# Riso9350e.net
KiCad netlist of a schematic drawn in EAGLE
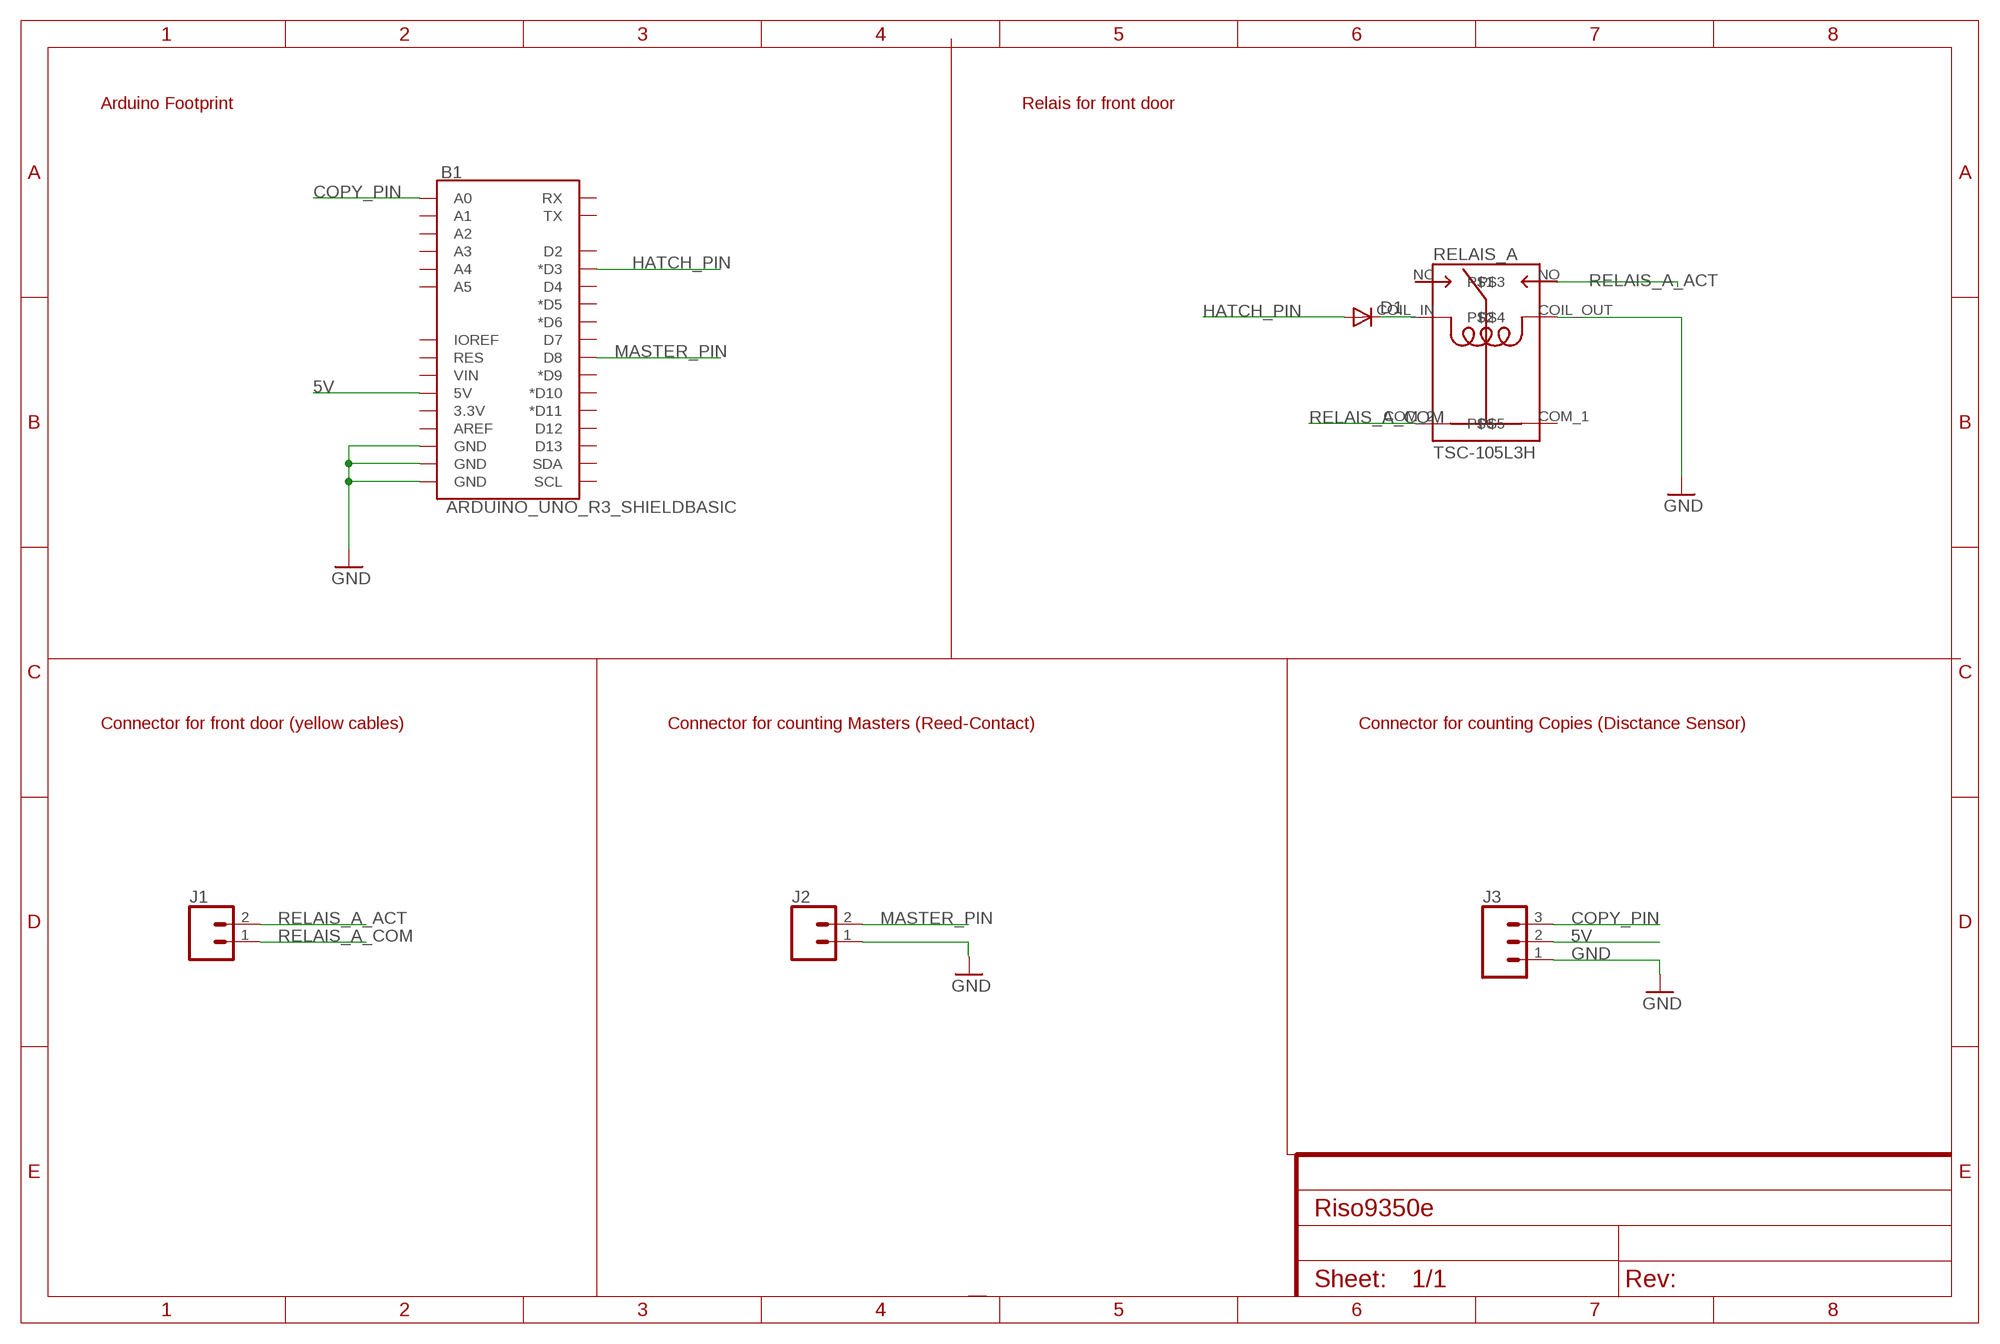
[diagram p0: schematic, sheet 1]

(export (version "E")
  (design (tool "Eeschema 10.0.6"))
  (components
    (comp (ref "B1")
      (value "ARDUINO_UNO_R3_SHIELDBASIC")
      (footprint "eagle-import:UNO_R3_SHIELD")
      (libsource (lib "eagle-import") (part "ARDUINO_UNO_R3_SHIELDBASIC"))
    )
    (comp (ref "D1")
      (value "DIODEPTH")
      (footprint "eagle-import:DIODE-1N4001")
      (libsource (lib "eagle-import") (part "DIODEPTH"))
    )
    (comp (ref "J1")
      (value "CONN_02")
      (footprint "eagle-import:1X02")
      (libsource (lib "eagle-import") (part "CONN_02"))
    )
    (comp (ref "J2")
      (value "CONN_02")
      (footprint "eagle-import:1X02")
      (libsource (lib "eagle-import") (part "CONN_02"))
    )
    (comp (ref "J3")
      (value "CONN_03")
      (footprint "eagle-import:1X03")
      (libsource (lib "eagle-import") (part "CONN_03"))
    )
    (comp (ref "RELAIS_A")
      (value "TSC-105L3H")
      (footprint "eagle-import:TSC_112L3H")
      (libsource (lib "eagle-import") (part "TSC-112L3H"))
    )
  )
  (nets
    (net (code "1") (name "/5V") (class "Default")
      (node (ref "B1") (pin "5V") (pinfunction "5V_5V") (pintype "bidirectional"))
      (node (ref "J3") (pin "2") (pinfunction "2_2") (pintype "passive"))
    )
    (net (code "2") (name "/COPY_PIN") (class "Default")
      (node (ref "B1") (pin "A0") (pinfunction "A0_A0") (pintype "bidirectional"))
      (node (ref "J3") (pin "3") (pinfunction "3_3") (pintype "passive"))
    )
    (net (code "3") (name "/HATCH_PIN") (class "Default")
      (node (ref "B1") (pin "D3") (pinfunction "*D3_D3") (pintype "bidirectional"))
      (node (ref "D1") (pin "A") (pinfunction "A_A") (pintype "passive"))
    )
    (net (code "4") (name "/MASTER_PIN") (class "Default")
      (node (ref "B1") (pin "D8") (pinfunction "D8_D8") (pintype "bidirectional"))
      (node (ref "J2") (pin "2") (pinfunction "2_2") (pintype "passive"))
    )
    (net (code "5") (name "/RELAIS_A_ACT") (class "Default")
      (node (ref "J1") (pin "2") (pinfunction "2_2") (pintype "passive"))
      (node (ref "RELAIS_A") (pin "NO") (pinfunction "P$3_NO") (pintype "bidirectional"))
    )
    (net (code "6") (name "/RELAIS_A_COM") (class "Default")
      (node (ref "J1") (pin "1") (pinfunction "1_1") (pintype "passive"))
      (node (ref "RELAIS_A") (pin "COM_2") (pinfunction "P$6_COM_2") (pintype "bidirectional"))
    )
    (net (code "7") (name "GND") (class "Default")
      (node (ref "B1") (pin "GND@0") (pinfunction "GND_GND@0") (pintype "bidirectional"))
      (node (ref "B1") (pin "GND@1") (pinfunction "GND_GND@1") (pintype "bidirectional"))
      (node (ref "B1") (pin "GND@2") (pinfunction "GND_GND@2") (pintype "bidirectional"))
      (node (ref "J2") (pin "1") (pinfunction "1_1") (pintype "passive"))
      (node (ref "J3") (pin "1") (pinfunction "1_1") (pintype "passive"))
      (node (ref "RELAIS_A") (pin "COIL_OUT") (pinfunction "P$4_COIL_OUT") (pintype "bidirectional"))
    )
    (net (code "8") (name "Net-(RELAIS_A-P$2)") (class "Default")
      (node (ref "D1") (pin "C") (pinfunction "C_C") (pintype "passive"))
      (node (ref "RELAIS_A") (pin "COIL_IN") (pinfunction "P$2_COIL_IN") (pintype "bidirectional"))
    )
    (net (code "9") (name "unconnected-(B1-*D5-PadD5)") (class "Default")
      (node (ref "B1") (pin "D5") (pinfunction "*D5_D5") (pintype "bidirectional"))
    )
    (net (code "10") (name "unconnected-(B1-*D6-PadD6)") (class "Default")
      (node (ref "B1") (pin "D6") (pinfunction "*D6_D6") (pintype "bidirectional"))
    )
    (net (code "11") (name "unconnected-(B1-*D9-PadD9)") (class "Default")
      (node (ref "B1") (pin "D9") (pinfunction "*D9_D9") (pintype "bidirectional"))
    )
    (net (code "12") (name "unconnected-(B1-*D10-PadD10)") (class "Default")
      (node (ref "B1") (pin "D10") (pinfunction "*D10_D10") (pintype "bidirectional"))
    )
    (net (code "13") (name "unconnected-(B1-*D11-PadD11)") (class "Default")
      (node (ref "B1") (pin "D11") (pinfunction "*D11_D11") (pintype "bidirectional"))
    )
    (net (code "14") (name "unconnected-(B1-Pad3.3V)") (class "Default")
      (node (ref "B1") (pin "3.3V") (pinfunction "3.3V_3.3V") (pintype "bidirectional"))
    )
    (net (code "15") (name "unconnected-(B1-PadA1)") (class "Default")
      (node (ref "B1") (pin "A1") (pinfunction "A1_A1") (pintype "bidirectional"))
    )
    (net (code "16") (name "unconnected-(B1-PadA2)") (class "Default")
      (node (ref "B1") (pin "A2") (pinfunction "A2_A2") (pintype "bidirectional"))
    )
    (net (code "17") (name "unconnected-(B1-PadA3)") (class "Default")
      (node (ref "B1") (pin "A3") (pinfunction "A3_A3") (pintype "bidirectional"))
    )
    (net (code "18") (name "unconnected-(B1-PadA4)") (class "Default")
      (node (ref "B1") (pin "A4") (pinfunction "A4_A4") (pintype "bidirectional"))
    )
    (net (code "19") (name "unconnected-(B1-PadA5)") (class "Default")
      (node (ref "B1") (pin "A5") (pinfunction "A5_A5") (pintype "bidirectional"))
    )
    (net (code "20") (name "unconnected-(B1-PadAREF)") (class "Default")
      (node (ref "B1") (pin "AREF") (pinfunction "AREF_AREF") (pintype "bidirectional"))
    )
    (net (code "21") (name "unconnected-(B1-PadD2)") (class "Default")
      (node (ref "B1") (pin "D2") (pinfunction "D2_D2") (pintype "bidirectional"))
    )
    (net (code "22") (name "unconnected-(B1-PadD4)") (class "Default")
      (node (ref "B1") (pin "D4") (pinfunction "D4_D4") (pintype "bidirectional"))
    )
    (net (code "23") (name "unconnected-(B1-PadD7)") (class "Default")
      (node (ref "B1") (pin "D7") (pinfunction "D7_D7") (pintype "bidirectional"))
    )
    (net (code "24") (name "unconnected-(B1-PadD12)") (class "Default")
      (node (ref "B1") (pin "D12") (pinfunction "D12_D12") (pintype "bidirectional"))
    )
    (net (code "25") (name "unconnected-(B1-PadD13)") (class "Default")
      (node (ref "B1") (pin "D13") (pinfunction "D13_D13") (pintype "bidirectional"))
    )
    (net (code "26") (name "unconnected-(B1-PadIOREF)") (class "Default")
      (node (ref "B1") (pin "IOREF") (pinfunction "IOREF_IOREF") (pintype "bidirectional"))
    )
    (net (code "27") (name "unconnected-(B1-PadRES)") (class "Default")
      (node (ref "B1") (pin "RES") (pinfunction "RES_RES") (pintype "bidirectional"))
    )
    (net (code "28") (name "unconnected-(B1-PadRX)") (class "Default")
      (node (ref "B1") (pin "RX") (pinfunction "RX_RX") (pintype "bidirectional"))
    )
    (net (code "29") (name "unconnected-(B1-PadSCL)") (class "Default")
      (node (ref "B1") (pin "SCL") (pinfunction "SCL_SCL") (pintype "bidirectional"))
    )
    (net (code "30") (name "unconnected-(B1-PadSDA)") (class "Default")
      (node (ref "B1") (pin "SDA") (pinfunction "SDA_SDA") (pintype "bidirectional"))
    )
    (net (code "31") (name "unconnected-(B1-PadTX)") (class "Default")
      (node (ref "B1") (pin "TX") (pinfunction "TX_TX") (pintype "bidirectional"))
    )
    (net (code "32") (name "unconnected-(B1-PadVIN)") (class "Default")
      (node (ref "B1") (pin "VIN") (pinfunction "VIN_VIN") (pintype "bidirectional"))
    )
    (net (code "33") (name "unconnected-(RELAIS_A-P$1-PadNC)") (class "Default")
      (node (ref "RELAIS_A") (pin "NC") (pinfunction "P$1_NC") (pintype "bidirectional"))
    )
    (net (code "34") (name "unconnected-(RELAIS_A-P$5-PadCOM_1)") (class "Default")
      (node (ref "RELAIS_A") (pin "COM_1") (pinfunction "P$5_COM_1") (pintype "bidirectional"))
    )
  )
)
